# Sheet1.net
KiCad netlist of a schematic drawn in Altium Designer
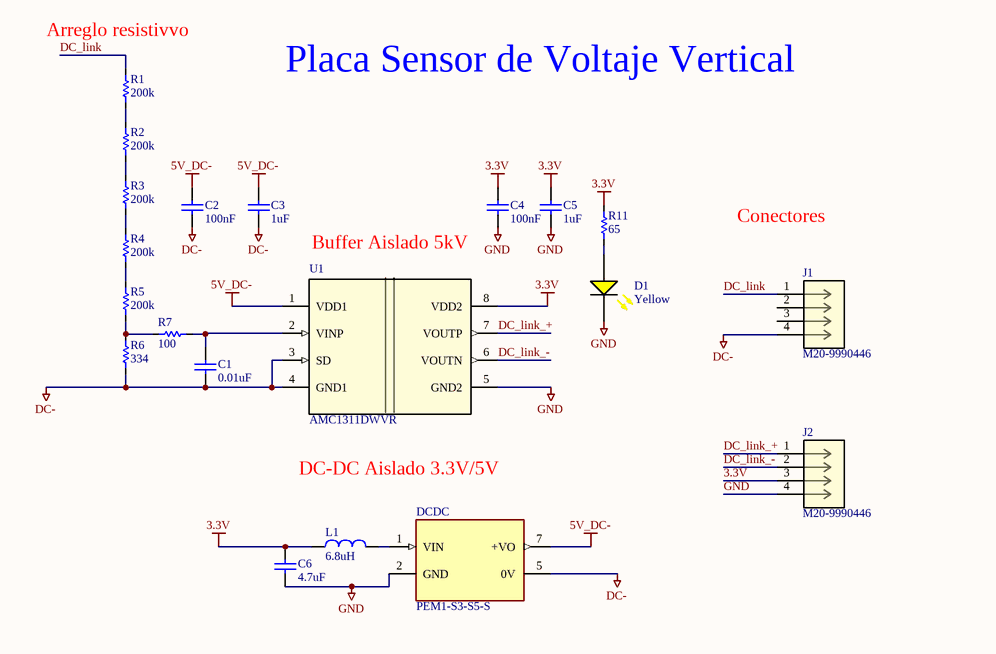
[diagram p0: Sheet1.SchDoc]

(export (version "E")
  (design (tool "Eeschema 10.0.6"))
  (components
    (comp (ref "C1")
      (value "0.01uF")
      (footprint "CAP_0603")
      (description "0.1µF ±10% 50V Ceramic Capacitor X7R 0603 (1608 Metric)")
      (fields (field (name "MF") "KEMET") (field (name "CREATED") "2020_06_15_DAarancibia"))
      (libsource (lib "Schlib1") (part "Cap_0603"))
    )
    (comp (ref "C2")
      (value "100nF")
      (footprint "CAP_0603")
      (description "0.1µF ±10% 50V Ceramic Capacitor X7R 0603 (1608 Metric)")
      (fields (field (name "MF") "KEMET") (field (name "CREATED") "2020_06_15_DAarancibia"))
      (libsource (lib "Schlib1") (part "Cap_0603"))
    )
    (comp (ref "C3")
      (value "1uF")
      (footprint "CAP_0603")
      (description "0.1µF ±10% 50V Ceramic Capacitor X7R 0603 (1608 Metric)")
      (fields (field (name "MF") "KEMET") (field (name "CREATED") "2020_06_15_DAarancibia"))
      (libsource (lib "Schlib1") (part "Cap_0603"))
    )
    (comp (ref "C4")
      (value "100nF")
      (footprint "CAP_0603")
      (description "0.1µF ±10% 50V Ceramic Capacitor X7R 0603 (1608 Metric)")
      (fields (field (name "MF") "KEMET") (field (name "CREATED") "2020_06_15_DAarancibia"))
      (libsource (lib "Schlib1") (part "Cap_0603"))
    )
    (comp (ref "C5")
      (value "1uF")
      (footprint "CAP_0603")
      (description "0.1µF ±10% 50V Ceramic Capacitor X7R 0603 (1608 Metric)")
      (fields (field (name "MF") "KEMET") (field (name "CREATED") "2020_06_15_DAarancibia"))
      (libsource (lib "Schlib1") (part "Cap_0603"))
    )
    (comp (ref "C6")
      (value "4.7uF")
      (footprint "CAP_0805")
      (description "0.1µF ±10% 50V Ceramic Capacitor X7R 0805 (2012 Metric)")
      (fields (field (name "MF") "KEMET") (field (name "CREATED") "2020_06_15_DAarancibia"))
      (libsource (lib "Schlib1") (part "Cap_0805"))
    )
    (comp (ref "D1")
      (value "Yellow")
      (footprint "LED_0603_Yellow")
      (description "Yellow 590nm LED Indication - Discrete 2V 0603 (1608 Metric)")
      (fields (field (name "MF") "Würth Elektronik") (field (name "CREATED") "2020_07_06_DAarancibia"))
      (libsource (lib "Schlib1") (part "Led_0603_Yellow"))
    )
    (comp (ref "DCDC")
      (value "PEM1-S3-S5-S")
      (footprint "CONV_PEM1-S3-S5-S")
      (description "12 Vdc, 0.083 A, 1 W, 10.8~13.2 Vdc Input Range")
      (libsource (lib "Schlib1") (part "PEM1-S3-S5-S"))
    )
    (comp (ref "J1")
      (value "M20-9990446")
      (footprint "CONN_M20_4_HRW")
      (description "No Description Available")
      (libsource (lib "Schlib1") (part "M20-9990446"))
    )
    (comp (ref "J2")
      (value "M20-9990446")
      (footprint "CONN_M20_4_HRW")
      (description "No Description Available")
      (libsource (lib "Schlib1") (part "M20-9990446"))
    )
    (comp (ref "L1")
      (value "6.8uH")
      (footprint "INDUCTOR_1210")
      (description "10µH Unshielded Wirewound Inductor 700mA 350mOhm Max 1210 (3225 Metric)")
      (fields (field (name "MF") "Taiyo Yuden") (field (name "CREATED") "2020_07_06_DAarancibia"))
      (libsource (lib "Schlib1") (part "Inductor_1210"))
    )
    (comp (ref "R1")
      (value "200k")
      (footprint "RES_0603")
      (fields
        (field (name "MF") "Panasonic Electronic Components")
        (field (name "CREATED") "2020_06_15_DAarancibia")
      )
      (libsource (lib "Schlib1") (part "Res_0603"))
    )
    (comp (ref "R2")
      (value "200k")
      (footprint "RES_0603")
      (fields
        (field (name "MF") "Panasonic Electronic Components")
        (field (name "CREATED") "2020_06_15_DAarancibia")
      )
      (libsource (lib "Schlib1") (part "Res_0603"))
    )
    (comp (ref "R3")
      (value "200k")
      (footprint "RES_0603")
      (fields
        (field (name "MF") "Panasonic Electronic Components")
        (field (name "CREATED") "2020_06_15_DAarancibia")
      )
      (libsource (lib "Schlib1") (part "Res_0603"))
    )
    (comp (ref "R4")
      (value "200k")
      (footprint "RES_0603")
      (fields
        (field (name "MF") "Panasonic Electronic Components")
        (field (name "CREATED") "2020_06_15_DAarancibia")
      )
      (libsource (lib "Schlib1") (part "Res_0603"))
    )
    (comp (ref "R5")
      (value "200k")
      (footprint "RES_0603")
      (fields
        (field (name "MF") "Panasonic Electronic Components")
        (field (name "CREATED") "2020_06_15_DAarancibia")
      )
      (libsource (lib "Schlib1") (part "Res_0603"))
    )
    (comp (ref "R6")
      (value "334")
      (footprint "RES_0603")
      (fields
        (field (name "MF") "Panasonic Electronic Components")
        (field (name "CREATED") "2020_06_15_DAarancibia")
      )
      (libsource (lib "Schlib1") (part "Res_0603"))
    )
    (comp (ref "R7")
      (value "100")
      (footprint "RES_0603")
      (fields
        (field (name "MF") "Panasonic Electronic Components")
        (field (name "CREATED") "2020_06_15_DAarancibia")
      )
      (libsource (lib "Schlib1") (part "Res_0603"))
    )
    (comp (ref "R11")
      (value "65")
      (footprint "RES_0603")
      (fields
        (field (name "MF") "Panasonic Electronic Components")
        (field (name "CREATED") "2020_06_15_DAarancibia")
      )
      (libsource (lib "Schlib1") (part "Res_0603"))
    )
    (comp (ref "U1")
      (value "AMC1311DWVR")
      (footprint "DWV0008A")
      (description "No Description Available")
      (libsource (lib "Schlib1") (part "AMC1311DWVR"))
    )
  )
  (nets
    (net (code "1") (name "/DC_link") (class "Default")
      (node (ref "J1") (pin "1") (pinfunction "1_1") (pintype "passive"))
      (node (ref "R1") (pin "2") (pinfunction "2_2") (pintype "passive"))
    )
    (net (code "2") (name "/DC_link_+") (class "Default")
      (node (ref "J2") (pin "1") (pinfunction "1_1") (pintype "passive"))
      (node (ref "U1") (pin "7") (pinfunction "VOUTP_7") (pintype "output"))
    )
    (net (code "3") (name "/DC_link_-") (class "Default")
      (node (ref "J2") (pin "2") (pinfunction "2_2") (pintype "passive"))
      (node (ref "U1") (pin "6") (pinfunction "VOUTN_6") (pintype "output"))
    )
    (net (code "4") (name "3.3V") (class "Default")
      (node (ref "C4") (pin "1") (pinfunction "1_1") (pintype "passive"))
      (node (ref "C5") (pin "1") (pinfunction "1_1") (pintype "passive"))
      (node (ref "C6") (pin "1") (pinfunction "1_1") (pintype "passive"))
      (node (ref "J2") (pin "3") (pinfunction "3_3") (pintype "passive"))
      (node (ref "L1") (pin "1") (pinfunction "1_1") (pintype "passive"))
      (node (ref "R11") (pin "2") (pinfunction "2_2") (pintype "passive"))
      (node (ref "U1") (pin "8") (pinfunction "VDD2_8") (pintype "power_in"))
    )
    (net (code "5") (name "5V_DC-") (class "Default")
      (node (ref "C2") (pin "1") (pinfunction "1_1") (pintype "passive"))
      (node (ref "C3") (pin "1") (pinfunction "1_1") (pintype "passive"))
      (node (ref "DCDC") (pin "7") (pinfunction "+VO_7") (pintype "output"))
      (node (ref "U1") (pin "1") (pinfunction "VDD1_1") (pintype "power_in"))
    )
    (net (code "6") (name "DC-") (class "Default")
      (node (ref "C1") (pin "2") (pinfunction "2_2") (pintype "passive"))
      (node (ref "C2") (pin "2") (pinfunction "2_2") (pintype "passive"))
      (node (ref "C3") (pin "2") (pinfunction "2_2") (pintype "passive"))
      (node (ref "DCDC") (pin "5") (pinfunction "0V_5") (pintype "power_in"))
      (node (ref "J1") (pin "4") (pinfunction "4_4") (pintype "passive"))
      (node (ref "R6") (pin "1") (pinfunction "1_1") (pintype "passive"))
      (node (ref "U1") (pin "3") (pinfunction "SD_3") (pintype "input"))
      (node (ref "U1") (pin "4") (pinfunction "GND1_4") (pintype "power_in"))
    )
    (net (code "7") (name "GND") (class "Default")
      (node (ref "C4") (pin "2") (pinfunction "2_2") (pintype "passive"))
      (node (ref "C5") (pin "2") (pinfunction "2_2") (pintype "passive"))
      (node (ref "C6") (pin "2") (pinfunction "2_2") (pintype "passive"))
      (node (ref "D1") (pin "2") (pinfunction "K_2") (pintype "passive"))
      (node (ref "DCDC") (pin "2") (pinfunction "GND_2") (pintype "power_in"))
      (node (ref "J2") (pin "4") (pinfunction "4_4") (pintype "passive"))
      (node (ref "U1") (pin "5") (pinfunction "GND2_5") (pintype "power_in"))
    )
    (net (code "8") (name "Net-(D1-A)") (class "Default")
      (node (ref "D1") (pin "1") (pinfunction "A_1") (pintype "passive"))
      (node (ref "R11") (pin "1") (pinfunction "1_1") (pintype "passive"))
    )
    (net (code "9") (name "Net-(DCDC-VIN)") (class "Default")
      (node (ref "DCDC") (pin "1") (pinfunction "VIN_1") (pintype "input"))
      (node (ref "L1") (pin "2") (pinfunction "2_2") (pintype "passive"))
    )
    (net (code "10") (name "Net-(R1-Pad1)") (class "Default")
      (node (ref "R1") (pin "1") (pinfunction "1_1") (pintype "passive"))
      (node (ref "R2") (pin "2") (pinfunction "2_2") (pintype "passive"))
    )
    (net (code "11") (name "Net-(R2-Pad1)") (class "Default")
      (node (ref "R2") (pin "1") (pinfunction "1_1") (pintype "passive"))
      (node (ref "R3") (pin "2") (pinfunction "2_2") (pintype "passive"))
    )
    (net (code "12") (name "Net-(R3-Pad1)") (class "Default")
      (node (ref "R3") (pin "1") (pinfunction "1_1") (pintype "passive"))
      (node (ref "R4") (pin "2") (pinfunction "2_2") (pintype "passive"))
    )
    (net (code "13") (name "Net-(R4-Pad1)") (class "Default")
      (node (ref "R4") (pin "1") (pinfunction "1_1") (pintype "passive"))
      (node (ref "R5") (pin "2") (pinfunction "2_2") (pintype "passive"))
    )
    (net (code "14") (name "Net-(R5-Pad1)") (class "Default")
      (node (ref "R5") (pin "1") (pinfunction "1_1") (pintype "passive"))
      (node (ref "R6") (pin "2") (pinfunction "2_2") (pintype "passive"))
      (node (ref "R7") (pin "2") (pinfunction "2_2") (pintype "passive"))
    )
    (net (code "15") (name "Net-(U1-VINP)") (class "Default")
      (node (ref "C1") (pin "1") (pinfunction "1_1") (pintype "passive"))
      (node (ref "R7") (pin "1") (pinfunction "1_1") (pintype "passive"))
      (node (ref "U1") (pin "2") (pinfunction "VINP_2") (pintype "input"))
    )
    (net (code "16") (name "unconnected-(J1-Pad2)") (class "Default")
      (node (ref "J1") (pin "2") (pinfunction "2_2") (pintype "passive"))
    )
    (net (code "17") (name "unconnected-(J1-Pad3)") (class "Default")
      (node (ref "J1") (pin "3") (pinfunction "3_3") (pintype "passive"))
    )
  )
)
